# power_supply.net
KiCad netlist of a schematic drawn in Altium Designer
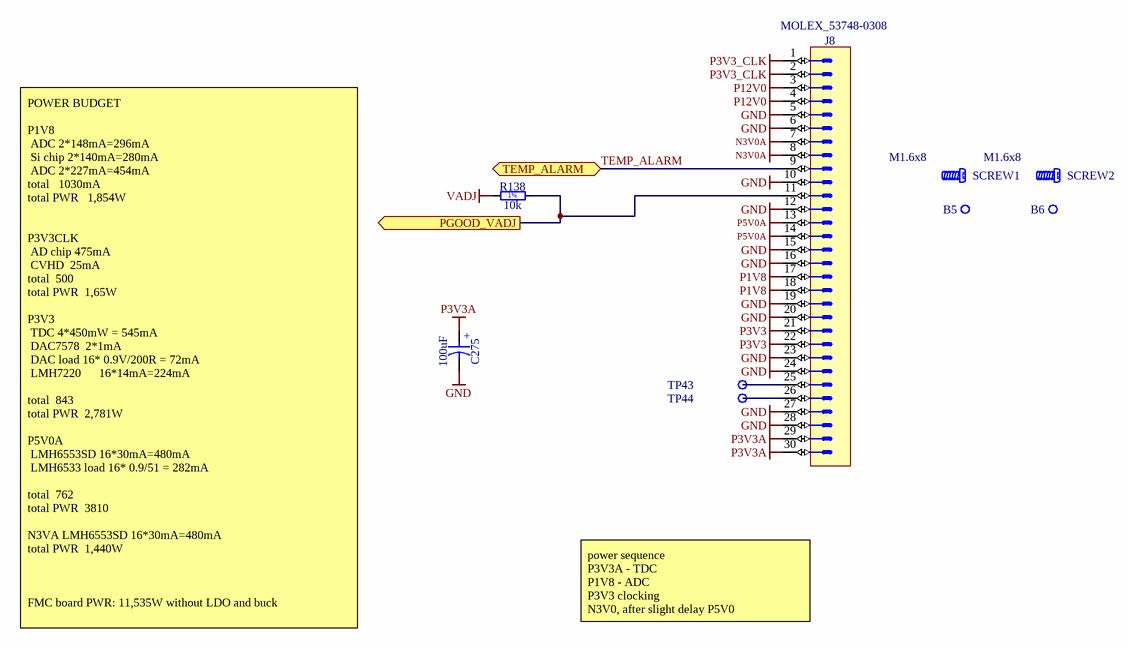
[diagram p0: power_supply.SchDoc]

(export (version "E")
  (design (tool "Eeschema 10.0.6"))
  (components
    (comp (ref "B5")
      (value "Plated Hole")
      (footprint "c300h160")
      (description "Single Terminal Socket")
      (fields (field (name "PART NUMBER") "PLATED_HOLE1.6_PAD3.0") (field (name "AUTHOR") "CERN DEM JMW"))
      (libsource (lib "Eletro-mechanical") (part "Single Terminal Socket"))
    )
    (comp (ref "B6")
      (value "Plated Hole")
      (footprint "c300h160")
      (description "Single Terminal Socket")
      (fields (field (name "PART NUMBER") "PLATED_HOLE1.6_PAD3.0") (field (name "AUTHOR") "CERN DEM JMW"))
      (libsource (lib "Eletro-mechanical") (part "Single Terminal Socket"))
    )
    (comp (ref "C275")
      (value "100uF")
      (footprint "CAPMP3216X180N")
      (description "Polarised capacitor")
      (fields
        (field (name "PART NUMBER") "CTE3216-18_100UF_6.3V_20%_ESR0500_AVX_TLJ")
        (field (name "VOLTAGE") "6.3V")
        (field (name "AUTHOR") "CERN DEM JLC")
      )
      (libsource (lib "Capacitors") (part "Capacitor - polarized"))
    )
    (comp (ref "J8")
      (value "SlimStack™")
      (footprint "MOLEX_53748-0308")
      (description "Connector 30 Male")
      (fields
        (field (name "PART NUMBER") "MOLEX_53748-0308")
        (field (name "MANUFACTURER") "MOLEX")
        (field (name "AUTHOR") "CERN DEM JLC")
      )
      (libsource (lib "Connectors") (part "Connector 30 Male"))
    )
    (comp (ref "R138")
      (value "10k")
      (footprint "RESC1005X40N")
      (description "Resistor - 1%")
      (fields
        (field (name "PART NUMBER") "R0402_10K_1%_0.0625W_100PPM")
        (field (name "POWER") "0.0625W")
        (field (name "AUTHOR") "CERN DEM JLC")
      )
      (libsource (lib "Resistors") (part "Resistor - 1%"))
    )
    (comp (ref "SCREW1")
      (value "M1.6x8")
      (footprint "BOSSARD_BN650-1243721_v")
      (description "Screw")
      (fields
        (field (name "PART NUMBER") "BOSSARD_BN650-1243721_v")
        (field (name "MANUFACTURER") "BOSSARD")
        (field (name "AUTHOR") "CERN DEM JMW")
      )
      (libsource (lib "Eletro-mechanical") (part "Screw"))
    )
    (comp (ref "SCREW2")
      (value "M1.6x8")
      (footprint "BOSSARD_BN650-1243721_v")
      (description "Screw")
      (fields
        (field (name "PART NUMBER") "BOSSARD_BN650-1243721_v")
        (field (name "MANUFACTURER") "BOSSARD")
        (field (name "AUTHOR") "CERN DEM JMW")
      )
      (libsource (lib "Eletro-mechanical") (part "Screw"))
    )
    (comp (ref "TP43")
      (value "Test Point")
      (footprint "TPS127")
      (fields (field (name "PART NUMBER") "SMD_PAD_1.27X1.27MM") (field (name "AUTHOR") "CERN DEM JLC"))
      (libsource (lib "Eletro-mechanical") (part "Test Point"))
    )
    (comp (ref "TP44")
      (value "Test Point")
      (footprint "TPS127")
      (fields (field (name "PART NUMBER") "SMD_PAD_1.27X1.27MM") (field (name "AUTHOR") "CERN DEM JLC"))
      (libsource (lib "Eletro-mechanical") (part "Test Point"))
    )
  )
  (nets
    (net (code "1") (name "/PGOOD_VADJ") (class "Default")
      (node (ref "J8") (pin "11") (pinfunction "11_11") (pintype "bidirectional"))
      (node (ref "R138") (pin "2") (pinfunction "2_2") (pintype "passive"))
    )
    (net (code "2") (name "/TEMP_ALARM") (class "Default")
      (node (ref "J8") (pin "9") (pinfunction "9_9") (pintype "bidirectional"))
    )
    (net (code "3") (name "GND") (class "Default")
      (node (ref "C275") (pin "2") (pinfunction "2_2") (pintype "passive"))
      (node (ref "J8") (pin "10") (pinfunction "10_10") (pintype "bidirectional"))
      (node (ref "J8") (pin "12") (pinfunction "12_12") (pintype "bidirectional"))
      (node (ref "J8") (pin "15") (pinfunction "15_15") (pintype "bidirectional"))
      (node (ref "J8") (pin "16") (pinfunction "16_16") (pintype "bidirectional"))
      (node (ref "J8") (pin "19") (pinfunction "19_19") (pintype "bidirectional"))
      (node (ref "J8") (pin "20") (pinfunction "20_20") (pintype "bidirectional"))
      (node (ref "J8") (pin "23") (pinfunction "23_23") (pintype "bidirectional"))
      (node (ref "J8") (pin "24") (pinfunction "24_24") (pintype "bidirectional"))
      (node (ref "J8") (pin "27") (pinfunction "27_27") (pintype "bidirectional"))
      (node (ref "J8") (pin "28") (pinfunction "28_28") (pintype "bidirectional"))
      (node (ref "J8") (pin "5") (pinfunction "5_5") (pintype "bidirectional"))
      (node (ref "J8") (pin "6") (pinfunction "6_6") (pintype "bidirectional"))
    )
    (net (code "4") (name "N3V0A") (class "Default")
      (node (ref "J8") (pin "7") (pinfunction "7_7") (pintype "bidirectional"))
      (node (ref "J8") (pin "8") (pinfunction "8_8") (pintype "bidirectional"))
    )
    (net (code "5") (name "Net-(J8-Pad25)") (class "Default")
      (node (ref "J8") (pin "25") (pinfunction "25_25") (pintype "bidirectional"))
      (node (ref "TP43") (pin "1") (pinfunction "1_1") (pintype "bidirectional"))
    )
    (net (code "6") (name "Net-(J8-Pad26)") (class "Default")
      (node (ref "J8") (pin "26") (pinfunction "26_26") (pintype "bidirectional"))
      (node (ref "TP44") (pin "1") (pinfunction "1_1") (pintype "bidirectional"))
    )
    (net (code "7") (name "P1V8") (class "Default")
      (node (ref "J8") (pin "17") (pinfunction "17_17") (pintype "bidirectional"))
      (node (ref "J8") (pin "18") (pinfunction "18_18") (pintype "bidirectional"))
    )
    (net (code "8") (name "P3V3") (class "Default")
      (node (ref "J8") (pin "21") (pinfunction "21_21") (pintype "bidirectional"))
      (node (ref "J8") (pin "22") (pinfunction "22_22") (pintype "bidirectional"))
    )
    (net (code "9") (name "P3V3A") (class "Default")
      (node (ref "C275") (pin "1") (pinfunction "1_1") (pintype "passive"))
      (node (ref "J8") (pin "29") (pinfunction "29_29") (pintype "bidirectional"))
      (node (ref "J8") (pin "30") (pinfunction "30_30") (pintype "bidirectional"))
    )
    (net (code "10") (name "P3V3_CLK") (class "Default")
      (node (ref "J8") (pin "1") (pinfunction "1_1") (pintype "bidirectional"))
      (node (ref "J8") (pin "2") (pinfunction "2_2") (pintype "bidirectional"))
    )
    (net (code "11") (name "P5V0A") (class "Default")
      (node (ref "J8") (pin "13") (pinfunction "13_13") (pintype "bidirectional"))
      (node (ref "J8") (pin "14") (pinfunction "14_14") (pintype "bidirectional"))
    )
    (net (code "12") (name "P12V0") (class "Default")
      (node (ref "J8") (pin "3") (pinfunction "3_3") (pintype "bidirectional"))
      (node (ref "J8") (pin "4") (pinfunction "4_4") (pintype "bidirectional"))
    )
    (net (code "13") (name "VADJ") (class "Default")
      (node (ref "R138") (pin "1") (pinfunction "1_1") (pintype "passive"))
    )
    (net (code "14") (name "unconnected-(B5-Pad1)") (class "Default")
      (node (ref "B5") (pin "1") (pinfunction "1_1") (pintype "bidirectional"))
    )
    (net (code "15") (name "unconnected-(B6-Pad1)") (class "Default")
      (node (ref "B6") (pin "1") (pinfunction "1_1") (pintype "bidirectional"))
    )
  )
)
